# InputAmplifier.net
KiCad netlist of a schematic drawn in Altium Designer
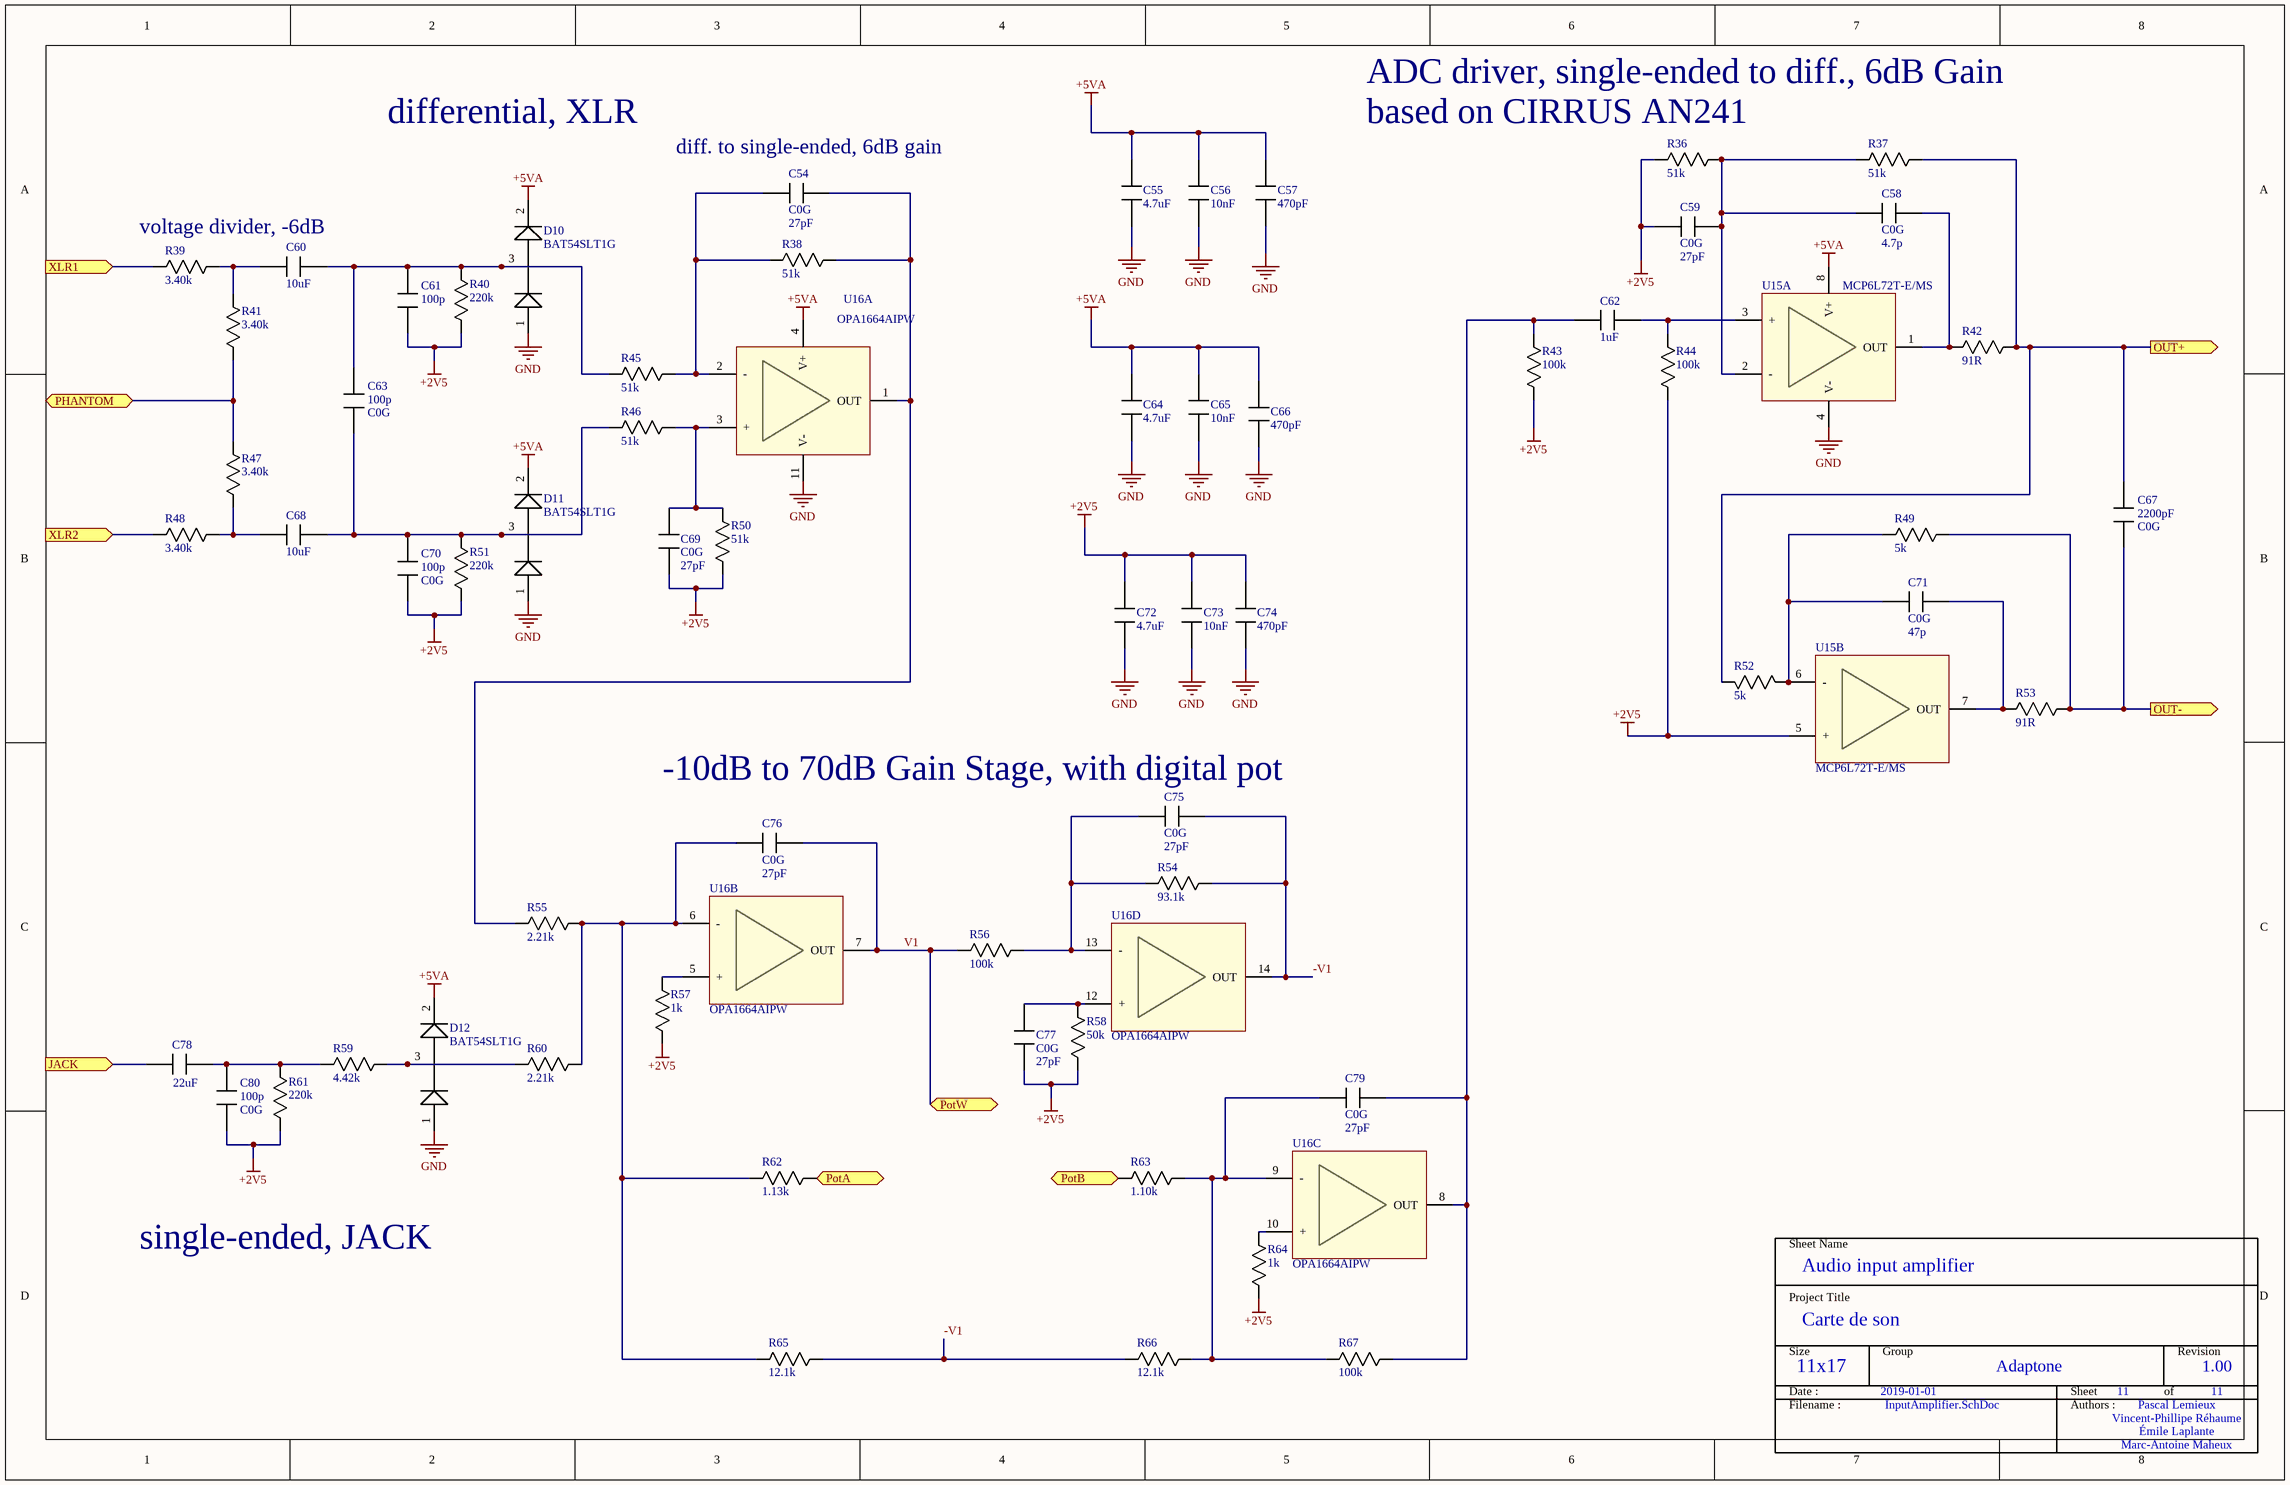
[diagram p0: InputAmplifier.SchDoc]

(export (version "E")
  (design (tool "Eeschema 10.0.6"))
  (components
    (comp (ref "C54")
      (value "27pF")
      (footprint "0402")
      (description "Capacitor")
      (fields (field (name "MFG") "Samsung") (field (name "TYPE") "C0G"))
      (libsource (lib "LIB_ADAPTONE_PASCAL_LEMIEUX") (part "Capacitor"))
    )
    (comp (ref "C55")
      (value "4.7uF")
      (footprint "0402")
      (description "Capacitor")
      (fields (field (name "MFG") "Samsung"))
      (libsource (lib "LIB_ADAPTONE_PASCAL_LEMIEUX") (part "Capacitor"))
    )
    (comp (ref "C56")
      (value "10nF")
      (footprint "0402")
      (description "Capacitor")
      (fields (field (name "MFG") "Samsung"))
      (libsource (lib "LIB_ADAPTONE_PASCAL_LEMIEUX") (part "Capacitor"))
    )
    (comp (ref "C57")
      (value "470pF")
      (footprint "0402")
      (description "Capacitor")
      (fields (field (name "MFG") "Murata"))
      (libsource (lib "LIB_ADAPTONE_PASCAL_LEMIEUX") (part "Capacitor"))
    )
    (comp (ref "C58")
      (value "4.7p")
      (footprint "0402")
      (description "Capacitor")
      (fields (field (name "MFG") "Samsung") (field (name "TYPE") "C0G"))
      (libsource (lib "LIB_ADAPTONE_PASCAL_LEMIEUX") (part "Capacitor"))
    )
    (comp (ref "C59")
      (value "27pF")
      (footprint "0402")
      (description "Capacitor")
      (fields (field (name "MFG") "Samsung") (field (name "TYPE") "C0G"))
      (libsource (lib "LIB_ADAPTONE_PASCAL_LEMIEUX") (part "Capacitor"))
    )
    (comp (ref "C60")
      (value "10uF")
      (footprint "CAP_1210")
      (description "Capacitor")
      (fields (field (name "MFG") "Samsung"))
      (libsource (lib "LIB_ADAPTONE_PASCAL_LEMIEUX") (part "Capacitor"))
    )
    (comp (ref "C61")
      (value "100p")
      (footprint "0402")
      (description "Capacitor")
      (fields (field (name "MFG") "Murata"))
      (libsource (lib "LIB_ADAPTONE_PASCAL_LEMIEUX") (part "Capacitor"))
    )
    (comp (ref "C62")
      (value "1uF")
      (footprint "0402")
      (description "Capacitor")
      (fields (field (name "MFG") "Samsung Electro-Mechanics"))
      (libsource (lib "LIB_ADAPTONE_PASCAL_LEMIEUX") (part "Capacitor"))
    )
    (comp (ref "C63")
      (value "100p")
      (footprint "0402")
      (description "Capacitor")
      (fields (field (name "MFG") "Yageo") (field (name "TYPE") "C0G"))
      (libsource (lib "LIB_ADAPTONE_PASCAL_LEMIEUX") (part "Capacitor"))
    )
    (comp (ref "C64")
      (value "4.7uF")
      (footprint "0402")
      (description "Capacitor")
      (fields (field (name "MFG") "Samsung"))
      (libsource (lib "LIB_ADAPTONE_PASCAL_LEMIEUX") (part "Capacitor"))
    )
    (comp (ref "C65")
      (value "10nF")
      (footprint "0402")
      (description "Capacitor")
      (fields (field (name "MFG") "Samsung"))
      (libsource (lib "LIB_ADAPTONE_PASCAL_LEMIEUX") (part "Capacitor"))
    )
    (comp (ref "C66")
      (value "470pF")
      (footprint "0402")
      (description "Capacitor")
      (fields (field (name "MFG") "Murata"))
      (libsource (lib "LIB_ADAPTONE_PASCAL_LEMIEUX") (part "Capacitor"))
    )
    (comp (ref "C67")
      (value "2200pF")
      (footprint "0603")
      (description "Capacitor")
      (fields (field (name "MFG") "Murata") (field (name "TYPE") "C0G"))
      (libsource (lib "ADAPTONE_CARTE_DE_SON") (part "Capacitor"))
    )
    (comp (ref "C68")
      (value "10uF")
      (footprint "CAP_1210")
      (description "Capacitor")
      (fields (field (name "MFG") "Samsung"))
      (libsource (lib "LIB_ADAPTONE_PASCAL_LEMIEUX") (part "Capacitor"))
    )
    (comp (ref "C69")
      (value "27pF")
      (footprint "0402")
      (description "Capacitor")
      (fields (field (name "MFG") "Samsung") (field (name "TYPE") "C0G"))
      (libsource (lib "LIB_ADAPTONE_PASCAL_LEMIEUX") (part "Capacitor"))
    )
    (comp (ref "C70")
      (value "100p")
      (footprint "0402")
      (description "Capacitor")
      (fields (field (name "MFG") "Yageo") (field (name "TYPE") "C0G"))
      (libsource (lib "LIB_ADAPTONE_PASCAL_LEMIEUX") (part "Capacitor"))
    )
    (comp (ref "C71")
      (value "47p")
      (footprint "0402")
      (description "Capacitor")
      (fields (field (name "MFG") "Samsung") (field (name "TYPE") "C0G"))
      (libsource (lib "LIB_ADAPTONE_PASCAL_LEMIEUX") (part "Capacitor"))
    )
    (comp (ref "C72")
      (value "4.7uF")
      (footprint "0402")
      (description "Capacitor")
      (fields (field (name "MFG") "Samsung"))
      (libsource (lib "LIB_ADAPTONE_PASCAL_LEMIEUX") (part "Capacitor"))
    )
    (comp (ref "C73")
      (value "10nF")
      (footprint "0402")
      (description "Capacitor")
      (fields (field (name "MFG") "Samsung"))
      (libsource (lib "LIB_ADAPTONE_PASCAL_LEMIEUX") (part "Capacitor"))
    )
    (comp (ref "C74")
      (value "470pF")
      (footprint "0402")
      (description "Capacitor")
      (fields (field (name "MFG") "Murata"))
      (libsource (lib "LIB_ADAPTONE_PASCAL_LEMIEUX") (part "Capacitor"))
    )
    (comp (ref "C75")
      (value "27pF")
      (footprint "0402")
      (description "Capacitor")
      (fields (field (name "MFG") "Samsung") (field (name "TYPE") "C0G"))
      (libsource (lib "LIB_ADAPTONE_PASCAL_LEMIEUX") (part "Capacitor"))
    )
    (comp (ref "C76")
      (value "27pF")
      (footprint "0402")
      (description "Capacitor")
      (fields (field (name "MFG") "Samsung") (field (name "TYPE") "C0G"))
      (libsource (lib "LIB_ADAPTONE_PASCAL_LEMIEUX") (part "Capacitor"))
    )
    (comp (ref "C77")
      (value "27pF")
      (footprint "0402")
      (description "Capacitor")
      (fields (field (name "MFG") "Samsung") (field (name "TYPE") "C0G"))
      (libsource (lib "LIB_ADAPTONE_PASCAL_LEMIEUX") (part "Capacitor"))
    )
    (comp (ref "C78")
      (value "22uF")
      (footprint "0805")
      (description "Capacitor")
      (fields (field (name "MFG") "Samsung Electro-Mechanics"))
      (libsource (lib "LIB_ADAPTONE_PASCAL_LEMIEUX") (part "Capacitor"))
    )
    (comp (ref "C79")
      (value "27pF")
      (footprint "0402")
      (description "Capacitor")
      (fields (field (name "MFG") "Samsung") (field (name "TYPE") "C0G"))
      (libsource (lib "LIB_ADAPTONE_PASCAL_LEMIEUX") (part "Capacitor"))
    )
    (comp (ref "C80")
      (value "100p")
      (footprint "0402")
      (description "Capacitor")
      (fields (field (name "MFG") "Yageo") (field (name "TYPE") "C0G"))
      (libsource (lib "LIB_ADAPTONE_PASCAL_LEMIEUX") (part "Capacitor"))
    )
    (comp (ref "D10")
      (value "Diode_dual")
      (footprint "SOT23_132")
      (description "Diode")
      (fields (field (name "MFG") "Onsemi") (field (name "MFG_PN") "BAT54SLT1G"))
      (libsource (lib "ADAPTONE_CARTE_DE_SON") (part "Diode_dual"))
    )
    (comp (ref "D11")
      (value "Diode_dual")
      (footprint "SOT23_132")
      (description "Diode")
      (fields (field (name "MFG") "Onsemi") (field (name "MFG_PN") "BAT54SLT1G"))
      (libsource (lib "ADAPTONE_CARTE_DE_SON") (part "Diode_dual"))
    )
    (comp (ref "D12")
      (value "Diode_dual")
      (footprint "SOT23_132")
      (description "Diode")
      (fields (field (name "MFG") "Onsemi") (field (name "MFG_PN") "BAT54SLT1G"))
      (libsource (lib "ADAPTONE_CARTE_DE_SON") (part "Diode_dual"))
    )
    (comp (ref "R36")
      (value "51k")
      (footprint "0402")
      (description "Resistor")
      (fields (field (name "MFG") "Yageo"))
      (libsource (lib "LIB_ADAPTONE_PASCAL_LEMIEUX") (part "Resistor"))
    )
    (comp (ref "R37")
      (value "51k")
      (footprint "0402")
      (description "Resistor")
      (fields (field (name "MFG") "Yageo"))
      (libsource (lib "LIB_ADAPTONE_PASCAL_LEMIEUX") (part "Resistor"))
    )
    (comp (ref "R38")
      (value "51k")
      (footprint "0402")
      (description "Resistor")
      (fields (field (name "MFG") "Yageo"))
      (libsource (lib "LIB_ADAPTONE_PASCAL_LEMIEUX") (part "Resistor"))
    )
    (comp (ref "R39")
      (value "3.40k")
      (footprint "0402")
      (description "Resistor")
      (fields (field (name "MFG") "Yageo"))
      (libsource (lib "LIB_ADAPTONE_PASCAL_LEMIEUX") (part "Resistor"))
    )
    (comp (ref "R40")
      (value "220k")
      (footprint "0402")
      (description "Resistor")
      (fields (field (name "MFG") "Yageo"))
      (libsource (lib "LIB_ADAPTONE_PASCAL_LEMIEUX") (part "Resistor"))
    )
    (comp (ref "R41")
      (value "3.40k")
      (footprint "0402")
      (description "Resistor")
      (fields (field (name "MFG") "Yageo"))
      (libsource (lib "LIB_ADAPTONE_PASCAL_LEMIEUX") (part "Resistor"))
    )
    (comp (ref "R42")
      (value "91R")
      (footprint "0402")
      (description "Resistor")
      (fields (field (name "MFG") "Yageo"))
      (libsource (lib "LIB_ADAPTONE_PASCAL_LEMIEUX") (part "Resistor"))
    )
    (comp (ref "R43")
      (value "100k")
      (footprint "0402")
      (description "Resistor")
      (fields (field (name "MFG") "Yageo"))
      (libsource (lib "LIB_ADAPTONE_PASCAL_LEMIEUX") (part "Resistor"))
    )
    (comp (ref "R44")
      (value "100k")
      (footprint "0402")
      (description "Resistor")
      (fields (field (name "MFG") "Yageo"))
      (libsource (lib "LIB_ADAPTONE_PASCAL_LEMIEUX") (part "Resistor"))
    )
    (comp (ref "R45")
      (value "51k")
      (footprint "0402")
      (description "Resistor")
      (fields (field (name "MFG") "Yageo"))
      (libsource (lib "LIB_ADAPTONE_PASCAL_LEMIEUX") (part "Resistor"))
    )
    (comp (ref "R46")
      (value "51k")
      (footprint "0402")
      (description "Resistor")
      (fields (field (name "MFG") "Yageo"))
      (libsource (lib "LIB_ADAPTONE_PASCAL_LEMIEUX") (part "Resistor"))
    )
    (comp (ref "R47")
      (value "3.40k")
      (footprint "0402")
      (description "Resistor")
      (fields (field (name "MFG") "Yageo"))
      (libsource (lib "LIB_ADAPTONE_PASCAL_LEMIEUX") (part "Resistor"))
    )
    (comp (ref "R48")
      (value "3.40k")
      (footprint "0402")
      (description "Resistor")
      (fields (field (name "MFG") "Yageo"))
      (libsource (lib "LIB_ADAPTONE_PASCAL_LEMIEUX") (part "Resistor"))
    )
    (comp (ref "R49")
      (value "5k")
      (footprint "0402")
      (description "Resistor")
      (fields (field (name "MFG") "Yageo"))
      (libsource (lib "LIB_ADAPTONE_PASCAL_LEMIEUX") (part "Resistor"))
    )
    (comp (ref "R50")
      (value "51k")
      (footprint "0402")
      (description "Resistor")
      (fields (field (name "MFG") "Yageo"))
      (libsource (lib "LIB_ADAPTONE_PASCAL_LEMIEUX") (part "Resistor"))
    )
    (comp (ref "R51")
      (value "220k")
      (footprint "0402")
      (description "Resistor")
      (fields (field (name "MFG") "Yageo"))
      (libsource (lib "LIB_ADAPTONE_PASCAL_LEMIEUX") (part "Resistor"))
    )
    (comp (ref "R52")
      (value "5k")
      (footprint "0402")
      (description "Resistor")
      (fields (field (name "MFG") "Yageo"))
      (libsource (lib "LIB_ADAPTONE_PASCAL_LEMIEUX") (part "Resistor"))
    )
    (comp (ref "R53")
      (value "91R")
      (footprint "0402")
      (description "Resistor")
      (fields (field (name "MFG") "Yageo"))
      (libsource (lib "LIB_ADAPTONE_PASCAL_LEMIEUX") (part "Resistor"))
    )
    (comp (ref "R54")
      (value "93.1k")
      (footprint "0402")
      (description "Resistor")
      (fields (field (name "MFG") "Yageo"))
      (libsource (lib "LIB_ADAPTONE_PASCAL_LEMIEUX") (part "Resistor"))
    )
    (comp (ref "R55")
      (value "2.21k")
      (footprint "0402")
      (description "Resistor")
      (fields (field (name "MFG") "Yageo"))
      (libsource (lib "LIB_ADAPTONE_PASCAL_LEMIEUX") (part "Resistor"))
    )
    (comp (ref "R56")
      (value "100k")
      (footprint "0402")
      (description "Resistor")
      (fields (field (name "MFG") "Yageo"))
      (libsource (lib "LIB_ADAPTONE_PASCAL_LEMIEUX") (part "Resistor"))
    )
    (comp (ref "R57")
      (value "1k")
      (footprint "0402")
      (description "Resistor")
      (fields (field (name "MFG") "Yageo"))
      (libsource (lib "LIB_ADAPTONE_PASCAL_LEMIEUX") (part "Resistor"))
    )
    (comp (ref "R58")
      (value "50k")
      (footprint "0402")
      (description "Resistor")
      (fields (field (name "MFG") "Yageo"))
      (libsource (lib "LIB_ADAPTONE_PASCAL_LEMIEUX") (part "Resistor"))
    )
    (comp (ref "R59")
      (value "4.42k")
      (footprint "0402")
      (description "Resistor")
      (fields (field (name "MFG") "Yageo"))
      (libsource (lib "LIB_ADAPTONE_PASCAL_LEMIEUX") (part "Resistor"))
    )
    (comp (ref "R60")
      (value "2.21k")
      (footprint "0402")
      (description "Resistor")
      (fields (field (name "MFG") "Yageo"))
      (libsource (lib "LIB_ADAPTONE_PASCAL_LEMIEUX") (part "Resistor"))
    )
    (comp (ref "R61")
      (value "220k")
      (footprint "0402")
      (description "Resistor")
      (fields (field (name "MFG") "Yageo"))
      (libsource (lib "LIB_ADAPTONE_PASCAL_LEMIEUX") (part "Resistor"))
    )
    (comp (ref "R62")
      (value "1.13k")
      (footprint "0402")
      (description "Resistor")
      (fields (field (name "MFG") "Yageo"))
      (libsource (lib "LIB_ADAPTONE_PASCAL_LEMIEUX") (part "Resistor"))
    )
    (comp (ref "R63")
      (value "1.10k")
      (footprint "0402")
      (description "Resistor")
      (fields (field (name "MFG") "Yageo"))
      (libsource (lib "LIB_ADAPTONE_PASCAL_LEMIEUX") (part "Resistor"))
    )
    (comp (ref "R64")
      (value "1k")
      (footprint "0402")
      (description "Resistor")
      (fields (field (name "MFG") "Yageo"))
      (libsource (lib "LIB_ADAPTONE_PASCAL_LEMIEUX") (part "Resistor"))
    )
    (comp (ref "R65")
      (value "12.1k")
      (footprint "0402")
      (description "Resistor")
      (fields (field (name "MFG") "Yageo"))
      (libsource (lib "LIB_ADAPTONE_PASCAL_LEMIEUX") (part "Resistor"))
    )
    (comp (ref "R66")
      (value "12.1k")
      (footprint "0402")
      (description "Resistor")
      (fields (field (name "MFG") "Yageo"))
      (libsource (lib "LIB_ADAPTONE_PASCAL_LEMIEUX") (part "Resistor"))
    )
    (comp (ref "R67")
      (value "100k")
      (footprint "0402")
      (description "Resistor")
      (fields (field (name "MFG") "Yageo"))
      (libsource (lib "LIB_ADAPTONE_PASCAL_LEMIEUX") (part "Resistor"))
    )
    (comp (ref "U15")
      (value "OPA_DUAL")
      (footprint "SOP127P600-8N")
      (description "Dual amplifier (standard)")
      (fields (field (name "MFG") "Microchip") (field (name "MFG_PN") "MCP6L72T-E/MS"))
      (libsource (lib "") (part "OPA_DUAL_1"))
    )
    (comp (ref "U16")
      (value "OPA1664")
      (footprint "14-TSSOP")
      (description "Quad amplifier (audio)")
      (fields (field (name "MFG") "Texas Instruments") (field (name "MFG_PN") "OPA1664AIPW"))
      (libsource (lib "") (part "OPA1664_1"))
    )
  )
  (nets
    (net (code "1") (name "+2V5") (class "Default")
      (node (ref "C59") (pin "2") (pintype "passive"))
      (node (ref "C61") (pin "2") (pintype "passive"))
      (node (ref "C69") (pin "1") (pintype "passive"))
      (node (ref "C70") (pin "2") (pintype "passive"))
      (node (ref "C72") (pin "1") (pintype "passive"))
      (node (ref "C73") (pin "1") (pintype "passive"))
      (node (ref "C74") (pin "1") (pintype "passive"))
      (node (ref "C77") (pin "1") (pintype "passive"))
      (node (ref "C80") (pin "2") (pintype "passive"))
      (node (ref "R36") (pin "1") (pintype "passive"))
      (node (ref "R40") (pin "2") (pintype "passive"))
      (node (ref "R43") (pin "1") (pintype "passive"))
      (node (ref "R44") (pin "1") (pintype "passive"))
      (node (ref "R50") (pin "2") (pintype "passive"))
      (node (ref "R51") (pin "2") (pintype "passive"))
      (node (ref "R57") (pin "1") (pintype "passive"))
      (node (ref "R58") (pin "2") (pintype "passive"))
      (node (ref "R61") (pin "2") (pintype "passive"))
      (node (ref "R64") (pin "1") (pintype "passive"))
      (node (ref "U15") (pin "5") (pinfunction "+_5") (pintype "passive"))
    )
    (net (code "2") (name "+5VA") (class "Default")
      (node (ref "C55") (pin "1") (pintype "passive"))
      (node (ref "C56") (pin "1") (pintype "passive"))
      (node (ref "C57") (pin "1") (pintype "passive"))
      (node (ref "C64") (pin "1") (pintype "passive"))
      (node (ref "C65") (pin "1") (pintype "passive"))
      (node (ref "C66") (pin "1") (pintype "passive"))
      (node (ref "D10") (pin "2") (pinfunction "K_2") (pintype "passive"))
      (node (ref "D11") (pin "2") (pinfunction "K_2") (pintype "passive"))
      (node (ref "D12") (pin "2") (pinfunction "K_2") (pintype "passive"))
      (node (ref "U15") (pin "8") (pinfunction "V+_8") (pintype "passive"))
      (node (ref "U16") (pin "4") (pinfunction "V+_4") (pintype "passive"))
    )
    (net (code "3") (name "/-V1") (class "Default")
      (node (ref "C75") (pin "2") (pintype "passive"))
      (node (ref "R54") (pin "1") (pintype "passive"))
      (node (ref "R65") (pin "1") (pintype "passive"))
      (node (ref "R66") (pin "2") (pintype "passive"))
      (node (ref "U16") (pin "14") (pinfunction "OUT_14") (pintype "passive"))
    )
    (net (code "4") (name "/JACK") (class "Default") (node (ref "C78") (pin "1") (pintype "passive")))
    (net (code "5") (name "/OUT+") (class "Default")
      (node (ref "C67") (pin "1") (pintype "passive"))
      (node (ref "R37") (pin "2") (pintype "passive"))
      (node (ref "R42") (pin "2") (pintype "passive"))
      (node (ref "R52") (pin "2") (pintype "passive"))
    )
    (net (code "6") (name "/OUT-") (class "Default")
      (node (ref "C67") (pin "2") (pintype "passive"))
      (node (ref "R49") (pin "2") (pintype "passive"))
      (node (ref "R53") (pin "2") (pintype "passive"))
    )
    (net (code "7") (name "/PHANTOM") (class "Default")
      (node (ref "R41") (pin "2") (pintype "passive"))
      (node (ref "R47") (pin "1") (pintype "passive"))
    )
    (net (code "8") (name "/PotA") (class "Default") (node (ref "R62") (pin "1") (pintype "passive")))
    (net (code "9") (name "/PotB") (class "Default") (node (ref "R63") (pin "2") (pintype "passive")))
    (net (code "10") (name "/V1") (class "Default")
      (node (ref "C76") (pin "2") (pintype "passive"))
      (node (ref "R56") (pin "1") (pintype "passive"))
      (node (ref "U16") (pin "7") (pinfunction "OUT_7") (pintype "passive"))
    )
    (net (code "11") (name "/XLR1") (class "Default") (node (ref "R39") (pin "1") (pintype "passive")))
    (net (code "12") (name "/XLR2") (class "Default") (node (ref "R48") (pin "1") (pintype "passive")))
    (net (code "13") (name "GND") (class "Default")
      (node (ref "C55") (pin "2") (pintype "passive"))
      (node (ref "C56") (pin "2") (pintype "passive"))
      (node (ref "C57") (pin "2") (pintype "passive"))
      (node (ref "C64") (pin "2") (pintype "passive"))
      (node (ref "C65") (pin "2") (pintype "passive"))
      (node (ref "C66") (pin "2") (pintype "passive"))
      (node (ref "C72") (pin "2") (pintype "passive"))
      (node (ref "C73") (pin "2") (pintype "passive"))
      (node (ref "C74") (pin "2") (pintype "passive"))
      (node (ref "D10") (pin "1") (pinfunction "K_1") (pintype "passive"))
      (node (ref "D11") (pin "1") (pinfunction "K_1") (pintype "passive"))
      (node (ref "D12") (pin "1") (pinfunction "K_1") (pintype "passive"))
      (node (ref "U15") (pin "4") (pinfunction "V-_4") (pintype "passive"))
      (node (ref "U16") (pin "11") (pinfunction "V-_11") (pintype "passive"))
    )
    (net (code "14") (name "Net-(C60-Pad1)") (class "Default")
      (node (ref "C60") (pin "1") (pintype "passive"))
      (node (ref "R39") (pin "2") (pintype "passive"))
      (node (ref "R41") (pin "1") (pintype "passive"))
    )
    (net (code "15") (name "Net-(C68-Pad1)") (class "Default")
      (node (ref "C68") (pin "1") (pintype "passive"))
      (node (ref "R47") (pin "2") (pintype "passive"))
      (node (ref "R48") (pin "2") (pintype "passive"))
    )
    (net (code "16") (name "Net-(C78-Pad2)") (class "Default")
      (node (ref "C78") (pin "2") (pintype "passive"))
      (node (ref "C80") (pin "1") (pintype "passive"))
      (node (ref "R59") (pin "2") (pintype "passive"))
      (node (ref "R61") (pin "1") (pintype "passive"))
    )
    (net (code "17") (name "Net-(D10-AK)") (class "Default")
      (node (ref "C60") (pin "2") (pintype "passive"))
      (node (ref "C61") (pin "1") (pintype "passive"))
      (node (ref "C63") (pin "1") (pintype "passive"))
      (node (ref "D10") (pin "3") (pinfunction "AK_3") (pintype "passive"))
      (node (ref "R40") (pin "1") (pintype "passive"))
      (node (ref "R45") (pin "1") (pintype "passive"))
    )
    (net (code "18") (name "Net-(D11-AK)") (class "Default")
      (node (ref "C63") (pin "2") (pintype "passive"))
      (node (ref "C68") (pin "2") (pintype "passive"))
      (node (ref "C70") (pin "1") (pintype "passive"))
      (node (ref "D11") (pin "3") (pinfunction "AK_3") (pintype "passive"))
      (node (ref "R46") (pin "1") (pintype "passive"))
      (node (ref "R51") (pin "1") (pintype "passive"))
    )
    (net (code "19") (name "Net-(D12-AK)") (class "Default")
      (node (ref "D12") (pin "3") (pinfunction "AK_3") (pintype "passive"))
      (node (ref "R59") (pin "1") (pintype "passive"))
      (node (ref "R60") (pin "2") (pintype "passive"))
    )
    (net (code "20") (name "Net-(U15A-+)") (class "Default")
      (node (ref "C62") (pin "2") (pintype "passive"))
      (node (ref "R44") (pin "2") (pintype "passive"))
      (node (ref "U15") (pin "3") (pinfunction "+_3") (pintype "passive"))
    )
    (net (code "21") (name "Net-(U15A--)") (class "Default")
      (node (ref "C58") (pin "1") (pintype "passive"))
      (node (ref "C59") (pin "1") (pintype "passive"))
      (node (ref "R36") (pin "2") (pintype "passive"))
      (node (ref "R37") (pin "1") (pintype "passive"))
      (node (ref "U15") (pin "2") (pinfunction "-_2") (pintype "passive"))
    )
    (net (code "22") (name "Net-(U15A-OUT)") (class "Default")
      (node (ref "C58") (pin "2") (pintype "passive"))
      (node (ref "R42") (pin "1") (pintype "passive"))
      (node (ref "U15") (pin "1") (pinfunction "OUT_1") (pintype "passive"))
    )
    (net (code "23") (name "Net-(U15B--)") (class "Default")
      (node (ref "C71") (pin "1") (pintype "passive"))
      (node (ref "R49") (pin "1") (pintype "passive"))
      (node (ref "R52") (pin "1") (pintype "passive"))
      (node (ref "U15") (pin "6") (pinfunction "-_6") (pintype "passive"))
    )
    (net (code "24") (name "Net-(U15B-OUT)") (class "Default")
      (node (ref "C71") (pin "2") (pintype "passive"))
      (node (ref "R53") (pin "1") (pintype "passive"))
      (node (ref "U15") (pin "7") (pinfunction "OUT_7") (pintype "passive"))
    )
    (net (code "25") (name "Net-(U16A-+)") (class "Default")
      (node (ref "C69") (pin "2") (pintype "passive"))
      (node (ref "R46") (pin "2") (pintype "passive"))
      (node (ref "R50") (pin "1") (pintype "passive"))
      (node (ref "U16") (pin "3") (pinfunction "+_3") (pintype "passive"))
    )
    (net (code "26") (name "Net-(U16A--)") (class "Default")
      (node (ref "C54") (pin "1") (pintype "passive"))
      (node (ref "R38") (pin "2") (pintype "passive"))
      (node (ref "R45") (pin "2") (pintype "passive"))
      (node (ref "U16") (pin "2") (pinfunction "-_2") (pintype "passive"))
    )
    (net (code "27") (name "Net-(U16A-OUT)") (class "Default")
      (node (ref "C54") (pin "2") (pintype "passive"))
      (node (ref "R38") (pin "1") (pintype "passive"))
      (node (ref "R55") (pin "2") (pintype "passive"))
      (node (ref "U16") (pin "1") (pinfunction "OUT_1") (pintype "passive"))
    )
    (net (code "28") (name "Net-(U16B-+)") (class "Default")
      (node (ref "R57") (pin "2") (pintype "passive"))
      (node (ref "U16") (pin "5") (pinfunction "+_5") (pintype "passive"))
    )
    (net (code "29") (name "Net-(U16B--)") (class "Default")
      (node (ref "C76") (pin "1") (pintype "passive"))
      (node (ref "R55") (pin "1") (pintype "passive"))
      (node (ref "R60") (pin "1") (pintype "passive"))
      (node (ref "R62") (pin "2") (pintype "passive"))
      (node (ref "R65") (pin "2") (pintype "passive"))
      (node (ref "U16") (pin "6") (pinfunction "-_6") (pintype "passive"))
    )
    (net (code "30") (name "Net-(U16C-+)") (class "Default")
      (node (ref "R64") (pin "2") (pintype "passive"))
      (node (ref "U16") (pin "10") (pinfunction "+_10") (pintype "passive"))
    )
    (net (code "31") (name "Net-(U16C--)") (class "Default")
      (node (ref "C79") (pin "1") (pintype "passive"))
      (node (ref "R63") (pin "1") (pintype "passive"))
      (node (ref "R66") (pin "1") (pintype "passive"))
      (node (ref "R67") (pin "2") (pintype "passive"))
      (node (ref "U16") (pin "9") (pinfunction "-_9") (pintype "passive"))
    )
    (net (code "32") (name "Net-(U16C-OUT)") (class "Default")
      (node (ref "C62") (pin "1") (pintype "passive"))
      (node (ref "C79") (pin "2") (pintype "passive"))
      (node (ref "R43") (pin "2") (pintype "passive"))
      (node (ref "R67") (pin "1") (pintype "passive"))
      (node (ref "U16") (pin "8") (pinfunction "OUT_8") (pintype "passive"))
    )
    (net (code "33") (name "Net-(U16D-+)") (class "Default")
      (node (ref "C77") (pin "2") (pintype "passive"))
      (node (ref "R58") (pin "1") (pintype "passive"))
      (node (ref "U16") (pin "12") (pinfunction "+_12") (pintype "passive"))
    )
    (net (code "34") (name "Net-(U16D--)") (class "Default")
      (node (ref "C75") (pin "1") (pintype "passive"))
      (node (ref "R54") (pin "2") (pintype "passive"))
      (node (ref "R56") (pin "2") (pintype "passive"))
      (node (ref "U16") (pin "13") (pinfunction "-_13") (pintype "passive"))
    )
  )
)
